# DS2482_shield.net
KiCad netlist of a schematic drawn in EAGLE
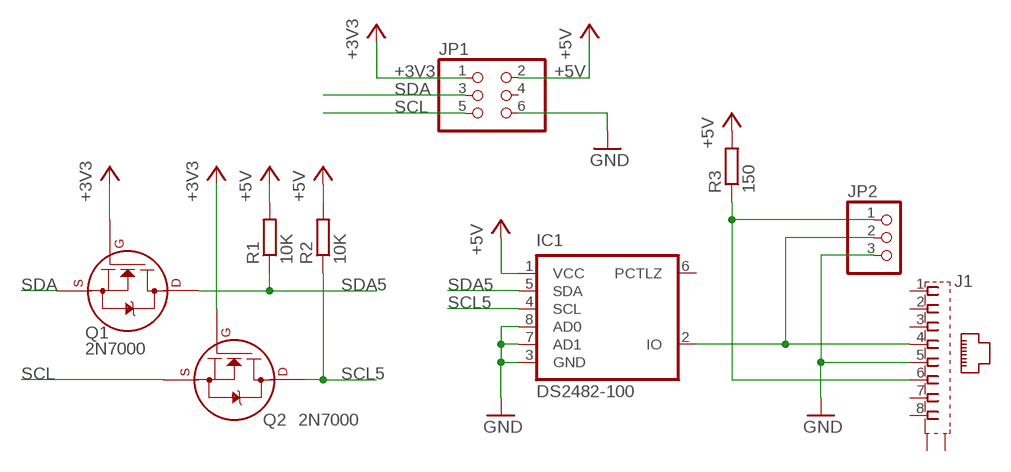
[diagram p0: schematic, sheet 1]

(export (version "E")
  (design (tool "Eeschema 10.0.6"))
  (components
    (comp (ref "IC1")
      (value "DS2482-100")
      (footprint "eagle-import:SO08")
      (libsource (lib "eagle-import") (part "DS2482-100"))
    )
    (comp (ref "J1")
      (value "555153-1")
      (footprint "eagle-import:555153-1")
      (libsource (lib "eagle-import") (part "555153-1"))
    )
    (comp (ref "JP1")
      (value "PINHD-2X3")
      (footprint "eagle-import:2X03")
      (libsource (lib "eagle-import") (part "PINHD-2X3"))
    )
    (comp (ref "JP2")
      (value "PINHD-1X3")
      (footprint "eagle-import:1X03")
      (libsource (lib "eagle-import") (part "PINHD-1X3"))
    )
    (comp (ref "Q1")
      (value "2N7000")
      (footprint "eagle-import:TO92-")
      (libsource (lib "eagle-import") (part "2N700_TO92-"))
    )
    (comp (ref "Q2")
      (value "2N7000")
      (footprint "eagle-import:TO92-")
      (libsource (lib "eagle-import") (part "2N700_TO92-"))
    )
    (comp (ref "R1")
      (value "10K")
      (footprint "eagle-import:0204_7")
      (libsource (lib "eagle-import") (part "R-EU_0204/7"))
    )
    (comp (ref "R2")
      (value "10K")
      (footprint "eagle-import:0204_7")
      (libsource (lib "eagle-import") (part "R-EU_0204/7"))
    )
    (comp (ref "R3")
      (value "150")
      (footprint "eagle-import:0204_7")
      (libsource (lib "eagle-import") (part "R-EU_0204/7"))
    )
  )
  (nets
    (net (code "1") (name "+3V3") (class "Default")
      (node (ref "JP1") (pin "1") (pinfunction "1_1") (pintype "passive"))
      (node (ref "Q1") (pin "2") (pinfunction "G_2") (pintype "tri_state"))
      (node (ref "Q2") (pin "2") (pinfunction "G_2") (pintype "tri_state"))
    )
    (net (code "2") (name "+5V") (class "Default")
      (node (ref "IC1") (pin "1") (pinfunction "VCC_1") (pintype "power_in"))
      (node (ref "JP1") (pin "2") (pinfunction "2_2") (pintype "passive"))
      (node (ref "R1") (pin "2") (pinfunction "2_2") (pintype "passive"))
      (node (ref "R2") (pin "2") (pinfunction "2_2") (pintype "passive"))
      (node (ref "R3") (pin "2") (pinfunction "2_2") (pintype "passive"))
    )
    (net (code "3") (name "/SCL") (class "Default")
      (node (ref "JP1") (pin "5") (pinfunction "5_5") (pintype "passive"))
      (node (ref "Q2") (pin "3") (pinfunction "S_3") (pintype "bidirectional"))
    )
    (net (code "4") (name "/SCL5") (class "Default")
      (node (ref "IC1") (pin "4") (pinfunction "SCL_4") (pintype "input"))
      (node (ref "Q2") (pin "1") (pinfunction "D_1") (pintype "bidirectional"))
      (node (ref "R2") (pin "1") (pinfunction "1_1") (pintype "passive"))
    )
    (net (code "5") (name "/SDA") (class "Default")
      (node (ref "JP1") (pin "3") (pinfunction "3_3") (pintype "passive"))
      (node (ref "Q1") (pin "3") (pinfunction "S_3") (pintype "bidirectional"))
    )
    (net (code "6") (name "/SDA5") (class "Default")
      (node (ref "IC1") (pin "5") (pinfunction "SDA_5") (pintype "input"))
      (node (ref "Q1") (pin "1") (pinfunction "D_1") (pintype "bidirectional"))
      (node (ref "R1") (pin "1") (pinfunction "1_1") (pintype "passive"))
    )
    (net (code "7") (name "GND") (class "Default")
      (node (ref "IC1") (pin "3") (pinfunction "GND_3") (pintype "power_in"))
      (node (ref "IC1") (pin "7") (pinfunction "AD1_7") (pintype "bidirectional"))
      (node (ref "IC1") (pin "8") (pinfunction "AD0_8") (pintype "bidirectional"))
      (node (ref "J1") (pin "5") (pinfunction "5_5") (pintype "passive"))
      (node (ref "JP1") (pin "6") (pinfunction "6_6") (pintype "passive"))
      (node (ref "JP2") (pin "3") (pinfunction "3_3") (pintype "passive"))
    )
    (net (code "8") (name "Net-(IC1-IO)") (class "Default")
      (node (ref "IC1") (pin "2") (pinfunction "IO_2") (pintype "bidirectional"))
      (node (ref "J1") (pin "4") (pinfunction "4_4") (pintype "passive"))
      (node (ref "JP2") (pin "2") (pinfunction "2_2") (pintype "passive"))
    )
    (net (code "9") (name "Net-(J1-Pad6)") (class "Default")
      (node (ref "J1") (pin "6") (pinfunction "6_6") (pintype "passive"))
      (node (ref "JP2") (pin "1") (pinfunction "1_1") (pintype "passive"))
      (node (ref "R3") (pin "1") (pinfunction "1_1") (pintype "passive"))
    )
    (net (code "10") (name "unconnected-(IC1-PCTLZ-Pad6)") (class "Default")
      (node (ref "IC1") (pin "6") (pinfunction "PCTLZ_6") (pintype "output"))
    )
    (net (code "11") (name "unconnected-(J1-Pad1)") (class "Default")
      (node (ref "J1") (pin "1") (pinfunction "1_1") (pintype "passive"))
    )
    (net (code "12") (name "unconnected-(J1-Pad2)") (class "Default")
      (node (ref "J1") (pin "2") (pinfunction "2_2") (pintype "passive"))
    )
    (net (code "13") (name "unconnected-(J1-Pad3)") (class "Default")
      (node (ref "J1") (pin "3") (pinfunction "3_3") (pintype "passive"))
    )
    (net (code "14") (name "unconnected-(J1-Pad7)") (class "Default")
      (node (ref "J1") (pin "7") (pinfunction "7_7") (pintype "passive"))
    )
    (net (code "15") (name "unconnected-(J1-Pad8)") (class "Default")
      (node (ref "J1") (pin "8") (pinfunction "8_8") (pintype "passive"))
    )
    (net (code "16") (name "unconnected-(J1-S1-PadG1)") (class "Default")
      (node (ref "J1") (pin "G1") (pinfunction "S1_G1") (pintype "passive"))
    )
    (net (code "17") (name "unconnected-(J1-S2-PadG2)") (class "Default")
      (node (ref "J1") (pin "G2") (pinfunction "S2_G2") (pintype "passive"))
    )
    (net (code "18") (name "unconnected-(JP1-Pad4)") (class "Default")
      (node (ref "JP1") (pin "4") (pinfunction "4_4") (pintype "passive"))
    )
  )
)
